# U_I_Meter_Bottom_ACS712.net
KiCad netlist of a schematic drawn in Altium Designer
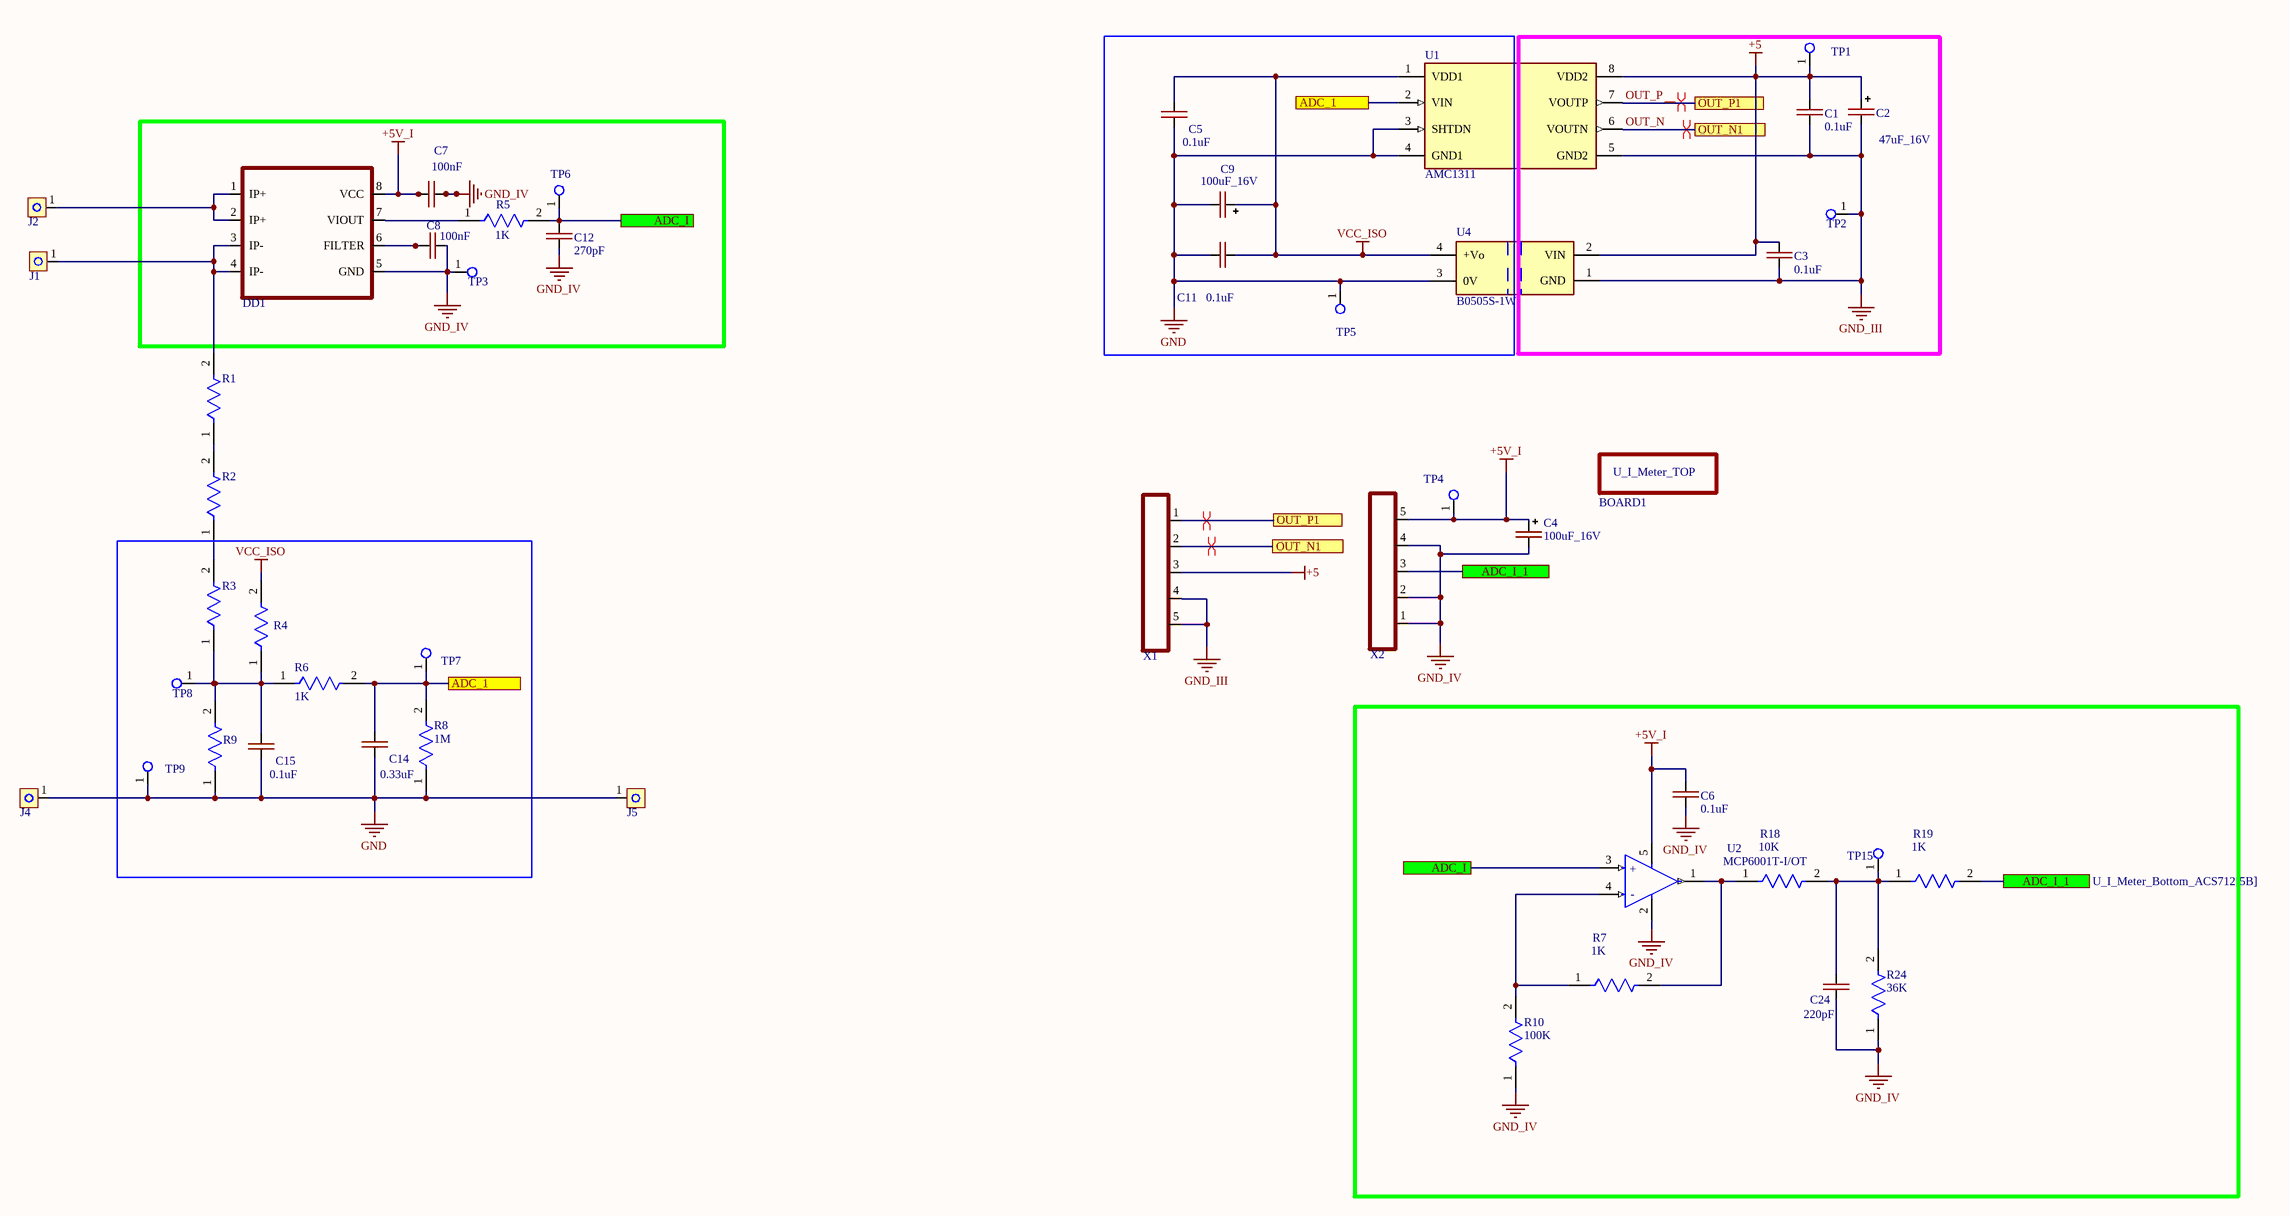
[diagram p0: U_I_Meter_Bottom_ACS712.SchDoc]

(export (version "E")
  (design (tool "Eeschema 10.0.6"))
  (components
    (comp (ref "BOARD1")
      (value "U_I_Meter_TOP")
      (footprint "U_I_Meter_TOP")
      (libsource (lib "U_I_Meter_TOP") (part "U_I_Meter_TOP"))
    )
    (comp (ref "C1")
      (value "0.1uF")
      (footprint "CAP-0805")
      (libsource (lib "PASSIVE_COMPONENTS") (part "CAP-NON-POLAR"))
    )
    (comp (ref "C2")
      (value "47uF_16V")
      (footprint "CAP-TAN-D")
      (libsource (lib "PASSIVE_COMPONENTS") (part "CAP-POLAR"))
    )
    (comp (ref "C3")
      (value "0.1uF")
      (footprint "CAP-0805")
      (libsource (lib "PASSIVE_COMPONENTS") (part "CAP-NON-POLAR"))
    )
    (comp (ref "C4")
      (value "100uF_16V")
      (footprint "CAP-TAN-D")
      (libsource (lib "PASSIVE_COMPONENTS") (part "CAP_POL_SMD"))
    )
    (comp (ref "C5")
      (value "0.1uF")
      (footprint "CAP-0805")
      (libsource (lib "PASSIVE_COMPONENTS") (part "CAP-NON-POLAR"))
    )
    (comp (ref "C6")
      (value "0.1uF")
      (footprint "CAP-0805")
      (libsource (lib "PASSIVE_COMPONENTS") (part "CAP-NON-POLAR"))
    )
    (comp (ref "C7")
      (value "100nF")
      (footprint "CAP-0805")
      (description "270pF")
      (libsource (lib "PASSIVE_COMPONENTS") (part "CAP-NON-POLAR"))
    )
    (comp (ref "C8")
      (value "100nF")
      (footprint "CAP-0805")
      (description "270pF")
      (libsource (lib "PASSIVE_COMPONENTS") (part "CAP-NON-POLAR"))
    )
    (comp (ref "C9")
      (value "100uF_16V")
      (footprint "CAP-TAN-D")
      (libsource (lib "PASSIVE_COMPONENTS") (part "CAP_POL_SMD"))
    )
    (comp (ref "C11")
      (value "0.1uF")
      (footprint "CAP-0805")
      (libsource (lib "PASSIVE_COMPONENTS") (part "CAP-NON-POLAR"))
    )
    (comp (ref "C12")
      (value "270pF")
      (footprint "CAP-0805")
      (libsource (lib "PASSIVE_COMPONENTS") (part "CAP-NON-POLAR"))
    )
    (comp (ref "C14")
      (value "0.33uF")
      (footprint "CAP-0805")
      (libsource (lib "PASSIVE_COMPONENTS") (part "CAP-NON-POLAR"))
    )
    (comp (ref "C15")
      (value "0.1uF")
      (footprint "CAP-0805")
      (libsource (lib "PASSIVE_COMPONENTS") (part "CAP-NON-POLAR"))
    )
    (comp (ref "C24")
      (value "220pF")
      (footprint "CAP-0805")
      (libsource (lib "PASSIVE_COMPONENTS") (part "CAP-NON-POLAR"))
    )
    (comp (ref "DD1") (value "ACS712") (footprint "SO8-150") (libsource (lib "ACS712") (part "ACS712")))
    (comp (ref "J1")
      (value "MG_136_HT")
      (footprint "Conn_MEIGAN_MG136HT")
      (libsource (lib "") (part "Connector_MEIGAN_MG136HT_1"))
    )
    (comp (ref "J2")
      (value "MG_136_HT")
      (footprint "Conn_MEIGAN_MG136HT")
      (libsource (lib "") (part "Connector_MEIGAN_MG136HT_1"))
    )
    (comp (ref "J4")
      (value "MG_136_HT")
      (footprint "Conn_MEIGAN_MG136HT")
      (libsource (lib "") (part "Connector_MEIGAN_MG136HT_1"))
    )
    (comp (ref "J5")
      (value "MG_136_HT")
      (footprint "Conn_MEIGAN_MG136HT")
      (libsource (lib "Connectors") (part "Connector_MEIGAN_MG136HT"))
    )
    (comp (ref "R1")
      (value "~")
      (footprint "RES-2512")
      (libsource (lib "PASSIVE_COMPONENTS") (part "RES-CONST"))
    )
    (comp (ref "R2")
      (value "~")
      (footprint "RES-2512")
      (libsource (lib "PASSIVE_COMPONENTS") (part "RES-CONST"))
    )
    (comp (ref "R3")
      (value "~")
      (footprint "RES-2512")
      (libsource (lib "PASSIVE_COMPONENTS") (part "RES-CONST"))
    )
    (comp (ref "R4")
      (value "~")
      (footprint "RES-0805")
      (libsource (lib "PASSIVE_COMPONENTS") (part "RES-CONST"))
    )
    (comp (ref "R5")
      (value "1K")
      (footprint "RES-0805")
      (libsource (lib "PASSIVE_COMPONENTS") (part "RES-CONST"))
    )
    (comp (ref "R6")
      (value "1K")
      (footprint "RES-0805")
      (libsource (lib "PASSIVE_COMPONENTS") (part "RES-CONST"))
    )
    (comp (ref "R7")
      (value "1K")
      (footprint "RES-0805")
      (description "10K")
      (libsource (lib "PASSIVE_COMPONENTS") (part "RES-CONST"))
    )
    (comp (ref "R8")
      (value "1M")
      (footprint "RES-0805")
      (libsource (lib "PASSIVE_COMPONENTS") (part "RES-CONST"))
    )
    (comp (ref "R9")
      (value "RES_1210")
      (footprint "RES_SMD_1210_IPC_B")
      (libsource (lib "PASSIVE_COMPONENTS") (part "RES_1210"))
    )
    (comp (ref "R10")
      (value "100K")
      (footprint "RES-0805")
      (libsource (lib "PASSIVE_COMPONENTS") (part "RES-CONST"))
    )
    (comp (ref "R18")
      (value "10K")
      (footprint "RES-0805")
      (libsource (lib "PASSIVE_COMPONENTS") (part "RES-CONST"))
    )
    (comp (ref "R19")
      (value "1K")
      (footprint "RES-0805")
      (description "10K")
      (libsource (lib "PASSIVE_COMPONENTS") (part "RES-CONST"))
    )
    (comp (ref "R24")
      (value "36K")
      (footprint "RES-0805")
      (libsource (lib "PASSIVE_COMPONENTS") (part "RES-CONST"))
    )
    (comp (ref "TP1")
      (value "Test_Point_PCB")
      (footprint "Test_Point")
      (description "Test_Point")
      (libsource (lib "Connectors") (part "TP_PCB?"))
    )
    (comp (ref "TP2")
      (value "Test_Point_PCB")
      (footprint "Test_Point")
      (description "Test_Point")
      (libsource (lib "Connectors") (part "TP_PCB?"))
    )
    (comp (ref "TP3")
      (value "Test_Point_PCB")
      (footprint "Test_Point")
      (description "Test_Point")
      (libsource (lib "Connectors") (part "TP_PCB?"))
    )
    (comp (ref "TP4")
      (value "Test_Point_PCB")
      (footprint "Test_Point")
      (description "Test_Point")
      (libsource (lib "Connectors") (part "TP_PCB?"))
    )
    (comp (ref "TP5")
      (value "Test_Point_PCB")
      (footprint "Pin_Test_Point(Pink)")
      (description "Test_Point")
      (libsource (lib "Connectors") (part "TP_PCB?"))
    )
    (comp (ref "TP6")
      (value "Test_Point_PCB")
      (footprint "Test_Point")
      (description "Test_Point")
      (libsource (lib "Connectors") (part "TP_PCB?"))
    )
    (comp (ref "TP7")
      (value "Test_Point_PCB")
      (footprint "Test_Point")
      (description "Test_Point")
      (libsource (lib "Connectors") (part "TP_PCB?"))
    )
    (comp (ref "TP8")
      (value "Test_Point_PCB")
      (footprint "Test_Point")
      (description "Test_Point")
      (libsource (lib "Connectors") (part "TP_PCB?"))
    )
    (comp (ref "TP9")
      (value "Test_Point_PCB")
      (footprint "Test_Point")
      (description "Test_Point")
      (libsource (lib "Connectors") (part "TP_PCB?"))
    )
    (comp (ref "TP15")
      (value "Test_Point_PCB")
      (footprint "Test_Point")
      (description "Test_Point")
      (libsource (lib "Connectors") (part "TP_PCB?"))
    )
    (comp (ref "U1")
      (value "AMC1311")
      (footprint "FP-DWV0008A-MFG")
      (libsource (lib "Integrated_Circuts") (part "AMC1311"))
    )
    (comp (ref "U2")
      (value "MCP6001T-I/OT")
      (footprint "SOT-23-5")
      (description "IC OPAMP GP 1 CIRCUIT SOT23-5")
      (fields (field (name "VOLTAGE") "6V"))
      (libsource (lib "Integrated_Circuts") (part "MCP6001T"))
    )
    (comp (ref "U4")
      (value "B0505S-1W")
      (footprint "B0505S-1W")
      (libsource (lib "Integrated_Circuts") (part "B0505S-1W"))
    )
    (comp (ref "X1")
      (value "CONN-5-PIN")
      (footprint "CONN-PLS-5-2.54mm")
      (libsource (lib "PLS-5__") (part "CONN-5-PIN"))
    )
    (comp (ref "X2")
      (value "CONN-5-PIN")
      (footprint "CONN-PLS-5-2.54mm")
      (libsource (lib "") (part "CONN-5-PIN_1"))
    )
  )
  (nets
    (net (code "1") (name "+5") (class "Default")
      (node (ref "C1") (pin "1") (pinfunction "1_1") (pintype "passive"))
      (node (ref "C2") (pin "1") (pinfunction "+_1") (pintype "passive"))
      (node (ref "C3") (pin "1") (pinfunction "1_1") (pintype "passive"))
      (node (ref "TP1") (pin "1") (pinfunction "G9_1") (pintype "passive"))
      (node (ref "U1") (pin "8") (pinfunction "VDD2_8") (pintype "power_in"))
      (node (ref "U4") (pin "2") (pinfunction "VIN_2") (pintype "power_in"))
      (node (ref "X1") (pin "3") (pinfunction "3_3") (pintype "passive"))
    )
    (net (code "2") (name "+5V_I") (class "Default")
      (node (ref "C4") (pin "1") (pinfunction "+_1") (pintype "passive"))
      (node (ref "C6") (pin "2") (pinfunction "2_2") (pintype "passive"))
      (node (ref "C7") (pin "1") (pinfunction "1_1") (pintype "passive"))
      (node (ref "DD1") (pin "8") (pinfunction "VCC_8") (pintype "passive"))
      (node (ref "TP4") (pin "1") (pinfunction "G9_1") (pintype "passive"))
      (node (ref "U2") (pin "5") (pinfunction "VDD_5") (pintype "power_in"))
      (node (ref "X2") (pin "5") (pinfunction "5_5") (pintype "passive"))
    )
    (net (code "3") (name "/ADC_1") (class "Default")
      (node (ref "C14") (pin "2") (pinfunction "2_2") (pintype "passive"))
      (node (ref "R6") (pin "2") (pinfunction "2_2") (pintype "passive"))
      (node (ref "R8") (pin "2") (pinfunction "2_2") (pintype "passive"))
      (node (ref "TP7") (pin "1") (pinfunction "G9_1") (pintype "passive"))
      (node (ref "U1") (pin "2") (pinfunction "VIN_2") (pintype "input"))
    )
    (net (code "4") (name "/ADC_I") (class "Default")
      (node (ref "C12") (pin "2") (pinfunction "2_2") (pintype "passive"))
      (node (ref "R5") (pin "2") (pinfunction "2_2") (pintype "passive"))
      (node (ref "TP6") (pin "1") (pinfunction "G9_1") (pintype "passive"))
      (node (ref "U2") (pin "3") (pinfunction "VIN+_3") (pintype "input"))
    )
    (net (code "5") (name "/ADC_I_1") (class "Default")
      (node (ref "R19") (pin "2") (pinfunction "2_2") (pintype "passive"))
      (node (ref "X2") (pin "3") (pinfunction "3_3") (pintype "passive"))
    )
    (net (code "6") (name "/OUT_N") (class "Default")
      (node (ref "U1") (pin "6") (pinfunction "VOUTN_6") (pintype "output"))
      (node (ref "X1") (pin "2") (pinfunction "2_2") (pintype "passive"))
    )
    (net (code "7") (name "/OUT_P") (class "Default")
      (node (ref "U1") (pin "7") (pinfunction "VOUTP_7") (pintype "output"))
      (node (ref "X1") (pin "1") (pinfunction "1_1") (pintype "passive"))
    )
    (net (code "8") (name "GND") (class "Default")
      (node (ref "C11") (pin "2") (pinfunction "2_2") (pintype "passive"))
      (node (ref "C14") (pin "1") (pinfunction "1_1") (pintype "passive"))
      (node (ref "C15") (pin "1") (pinfunction "1_1") (pintype "passive"))
      (node (ref "C5") (pin "1") (pinfunction "1_1") (pintype "passive"))
      (node (ref "C9") (pin "2") (pinfunction "-_2") (pintype "passive"))
      (node (ref "J4") (pin "1") (pinfunction "17_1") (pintype "passive"))
      (node (ref "J5") (pin "1") (pinfunction "17_1") (pintype "passive"))
      (node (ref "R8") (pin "1") (pinfunction "1_1") (pintype "passive"))
      (node (ref "R9") (pin "1") (pinfunction "1_1") (pintype "passive"))
      (node (ref "TP5") (pin "1") (pinfunction "G9_1") (pintype "passive"))
      (node (ref "TP9") (pin "1") (pinfunction "G9_1") (pintype "passive"))
      (node (ref "U1") (pin "3") (pinfunction "SHTDN_3") (pintype "input"))
      (node (ref "U1") (pin "4") (pinfunction "GND1_4") (pintype "power_in"))
      (node (ref "U4") (pin "3") (pinfunction "0V_3") (pintype "power_in"))
    )
    (net (code "9") (name "GND_III") (class "Default")
      (node (ref "C1") (pin "2") (pinfunction "2_2") (pintype "passive"))
      (node (ref "C2") (pin "2") (pinfunction "-_2") (pintype "passive"))
      (node (ref "C3") (pin "2") (pinfunction "2_2") (pintype "passive"))
      (node (ref "TP2") (pin "1") (pinfunction "G9_1") (pintype "passive"))
      (node (ref "U1") (pin "5") (pinfunction "GND2_5") (pintype "power_in"))
      (node (ref "U4") (pin "1") (pinfunction "GND_1") (pintype "power_in"))
      (node (ref "X1") (pin "4") (pinfunction "4_4") (pintype "passive"))
      (node (ref "X1") (pin "5") (pinfunction "5_5") (pintype "passive"))
    )
    (net (code "10") (name "GND_IV") (class "Default")
      (node (ref "C12") (pin "1") (pinfunction "1_1") (pintype "passive"))
      (node (ref "C24") (pin "1") (pinfunction "1_1") (pintype "passive"))
      (node (ref "C4") (pin "2") (pinfunction "-_2") (pintype "passive"))
      (node (ref "C6") (pin "1") (pinfunction "1_1") (pintype "passive"))
      (node (ref "C7") (pin "2") (pinfunction "2_2") (pintype "passive"))
      (node (ref "C8") (pin "2") (pinfunction "2_2") (pintype "passive"))
      (node (ref "DD1") (pin "5") (pinfunction "GND_5") (pintype "passive"))
      (node (ref "R10") (pin "1") (pinfunction "1_1") (pintype "passive"))
      (node (ref "R24") (pin "1") (pinfunction "1_1") (pintype "passive"))
      (node (ref "TP3") (pin "1") (pinfunction "G9_1") (pintype "passive"))
      (node (ref "U2") (pin "2") (pinfunction "VSS_2") (pintype "power_in"))
      (node (ref "X2") (pin "1") (pinfunction "1_1") (pintype "passive"))
      (node (ref "X2") (pin "2") (pinfunction "2_2") (pintype "passive"))
      (node (ref "X2") (pin "4") (pinfunction "4_4") (pintype "passive"))
    )
    (net (code "11") (name "Net-(DD1-FILTER)") (class "Default")
      (node (ref "C8") (pin "1") (pinfunction "1_1") (pintype "passive"))
      (node (ref "DD1") (pin "6") (pinfunction "FILTER_6") (pintype "passive"))
    )
    (net (code "12") (name "Net-(DD1-VIOUT)") (class "Default")
      (node (ref "DD1") (pin "7") (pinfunction "VIOUT_7") (pintype "passive"))
      (node (ref "R5") (pin "1") (pinfunction "1_1") (pintype "passive"))
    )
    (net (code "13") (name "Net-(J1-17)") (class "Default")
      (node (ref "DD1") (pin "3") (pinfunction "IP-_3") (pintype "passive"))
      (node (ref "DD1") (pin "4") (pinfunction "IP-_4") (pintype "passive"))
      (node (ref "J1") (pin "1") (pinfunction "17_1") (pintype "passive"))
      (node (ref "R1") (pin "2") (pinfunction "2_2") (pintype "passive"))
    )
    (net (code "14") (name "Net-(J2-17)") (class "Default")
      (node (ref "DD1") (pin "1") (pinfunction "IP+_1") (pintype "passive"))
      (node (ref "DD1") (pin "2") (pinfunction "IP+_2") (pintype "passive"))
      (node (ref "J2") (pin "1") (pinfunction "17_1") (pintype "passive"))
    )
    (net (code "15") (name "Net-(R1-Pad1)") (class "Default")
      (node (ref "R1") (pin "1") (pinfunction "1_1") (pintype "passive"))
      (node (ref "R2") (pin "2") (pinfunction "2_2") (pintype "passive"))
    )
    (net (code "16") (name "Net-(R2-Pad1)") (class "Default")
      (node (ref "R2") (pin "1") (pinfunction "1_1") (pintype "passive"))
      (node (ref "R3") (pin "2") (pinfunction "2_2") (pintype "passive"))
    )
    (net (code "17") (name "Net-(TP8-G9)") (class "Default")
      (node (ref "C15") (pin "2") (pinfunction "2_2") (pintype "passive"))
      (node (ref "R3") (pin "1") (pinfunction "1_1") (pintype "passive"))
      (node (ref "R4") (pin "1") (pinfunction "1_1") (pintype "passive"))
      (node (ref "R6") (pin "1") (pinfunction "1_1") (pintype "passive"))
      (node (ref "R9") (pin "2") (pinfunction "2_2") (pintype "passive"))
      (node (ref "TP8") (pin "1") (pinfunction "G9_1") (pintype "passive"))
    )
    (net (code "18") (name "Net-(TP15-G9)") (class "Default")
      (node (ref "C24") (pin "2") (pinfunction "2_2") (pintype "passive"))
      (node (ref "R18") (pin "2") (pinfunction "2_2") (pintype "passive"))
      (node (ref "R19") (pin "1") (pinfunction "1_1") (pintype "passive"))
      (node (ref "R24") (pin "2") (pinfunction "2_2") (pintype "passive"))
      (node (ref "TP15") (pin "1") (pinfunction "G9_1") (pintype "passive"))
    )
    (net (code "19") (name "Net-(U2-VIN-)") (class "Default")
      (node (ref "R10") (pin "2") (pinfunction "2_2") (pintype "passive"))
      (node (ref "R7") (pin "1") (pinfunction "1_1") (pintype "passive"))
      (node (ref "U2") (pin "4") (pinfunction "VIN-_4") (pintype "input"))
    )
    (net (code "20") (name "Net-(U2-VOUT)") (class "Default")
      (node (ref "R18") (pin "1") (pinfunction "1_1") (pintype "passive"))
      (node (ref "R7") (pin "2") (pinfunction "2_2") (pintype "passive"))
      (node (ref "U2") (pin "1") (pinfunction "VOUT_1") (pintype "output"))
    )
    (net (code "21") (name "VCC_ISO") (class "Default")
      (node (ref "C11") (pin "1") (pinfunction "1_1") (pintype "passive"))
      (node (ref "C5") (pin "2") (pinfunction "2_2") (pintype "passive"))
      (node (ref "C9") (pin "1") (pinfunction "+_1") (pintype "passive"))
      (node (ref "R4") (pin "2") (pinfunction "2_2") (pintype "passive"))
      (node (ref "U1") (pin "1") (pinfunction "VDD1_1") (pintype "power_in"))
      (node (ref "U4") (pin "4") (pinfunction "+Vo_4") (pintype "power_in"))
    )
  )
)
